# ProDoc___2025-09-02.net
KiCad netlist of a schematic drawn in EasyEDA Pro
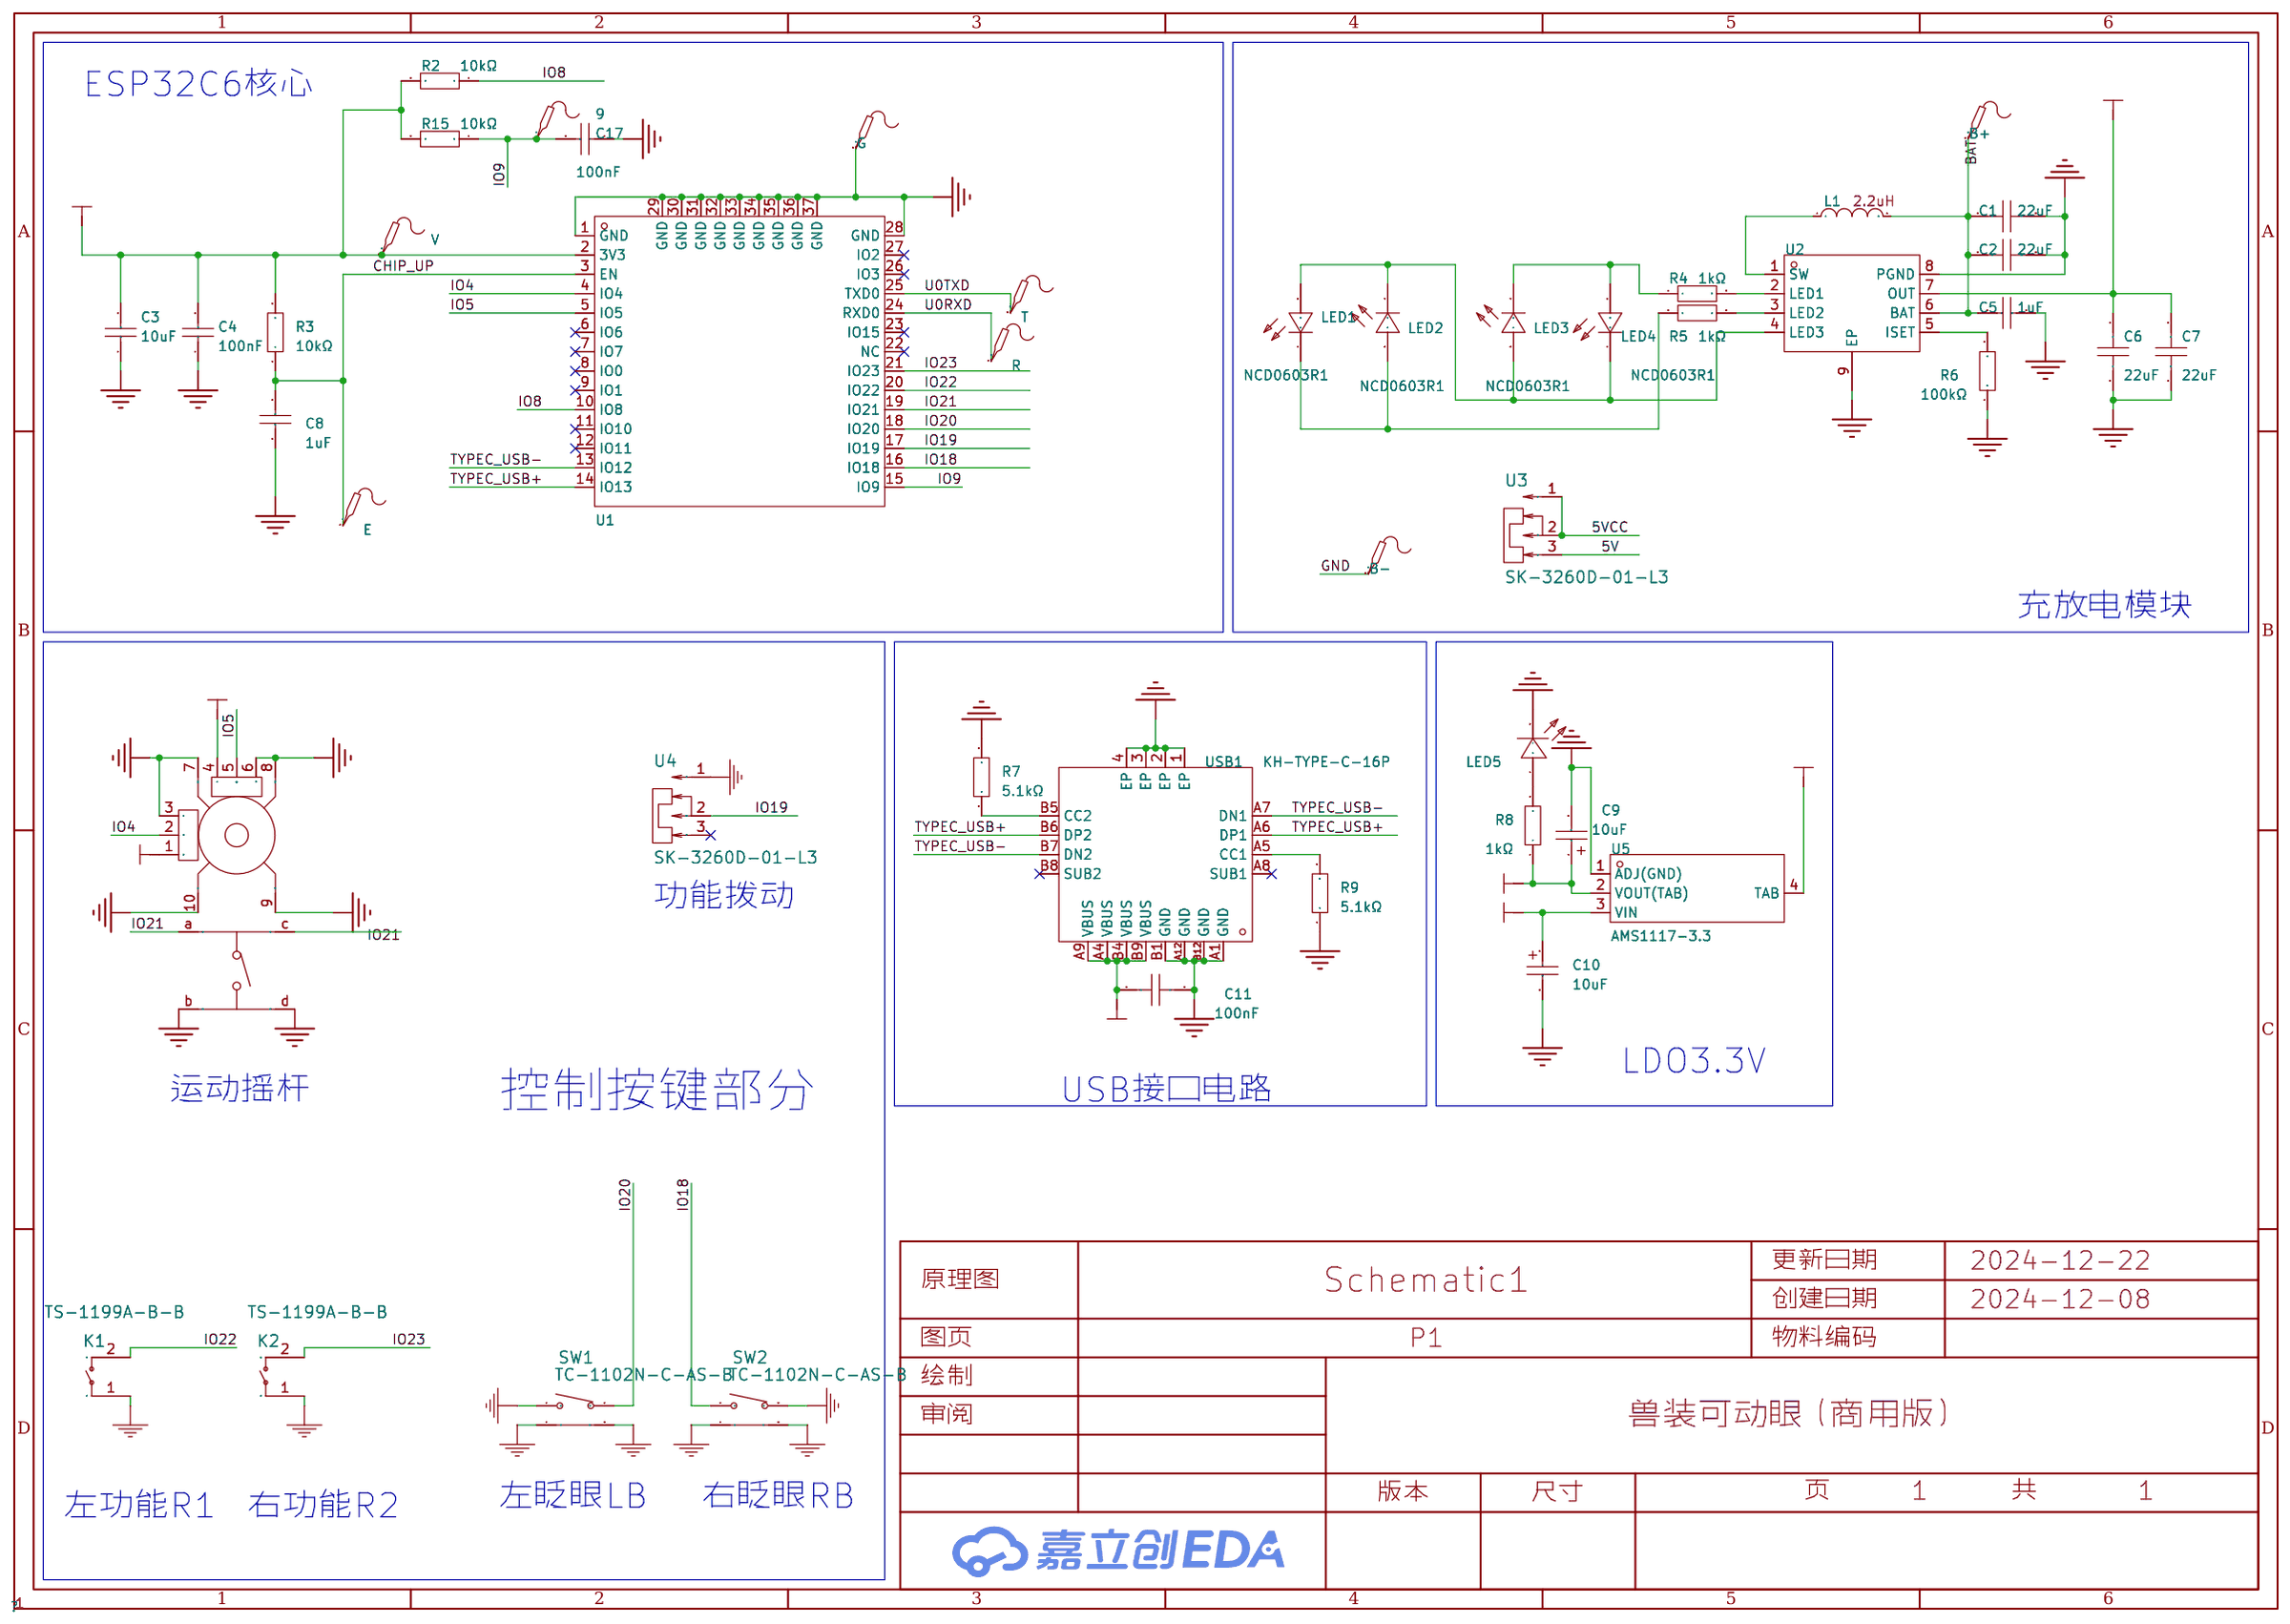
[diagram p0: schematic sheet]

(export (version "E")
  (design (tool "Eeschema 10.0.6"))
  (components
    (comp (ref "9")
      (value "~")
      (footprint "easyedapro:Test-Point-0.5mm")
      (description "Test Point 测试点")
      (libsource (lib "easyedapro") (part "Test-Point"))
    )
    (comp (ref "B+")
      (value "~")
      (footprint "easyedapro:Test-Point-0.5mm")
      (description "Test Point 测试点")
      (libsource (lib "easyedapro") (part "Test-Point"))
    )
    (comp (ref "B-")
      (value "~")
      (footprint "easyedapro:Test-Point-0.5mm")
      (description "Test Point 测试点")
      (libsource (lib "easyedapro") (part "Test-Point"))
    )
    (comp (ref "C1")
      (value "22uF")
      (footprint "easyedapro:C0805")
      (description "容值:22uF;精度:±20%;额定电压:25V;材质(温度系数):X5R;")
      (fields
        (field (name "Manufacturer Part") "CL21A226MAQNNNE")
        (field (name "Manufacturer") "SAMSUNG(三星)")
      )
      (libsource (lib "easyedapro") (part "CL21A226MAQNNNE"))
    )
    (comp (ref "C2")
      (value "22uF")
      (footprint "easyedapro:C0805")
      (description "容值:22uF;精度:±20%;额定电压:25V;材质(温度系数):X5R;")
      (fields
        (field (name "Manufacturer Part") "CL21A226MAQNNNE")
        (field (name "Manufacturer") "SAMSUNG(三星)")
      )
      (libsource (lib "easyedapro") (part "CL21A226MAQNNNE"))
    )
    (comp (ref "C3")
      (value "10uF")
      (footprint "easyedapro:C0805")
      (description "容值:10uF;精度:±10%;额定电压:16V;材质(温度系数):X5R;")
      (fields
        (field (name "Manufacturer Part") "CL21A106KOQNNNE")
        (field (name "Manufacturer") "SAMSUNG(三星)")
      )
      (libsource (lib "easyedapro") (part "CL21A106KOQNNNE"))
    )
    (comp (ref "C4")
      (value "100nF")
      (footprint "easyedapro:C0805")
      (description "容值:100nF;精度:±10%;额定电压:50V;材质(温度系数):X7R;")
      (fields (field (name "Manufacturer Part") "0805B104K500NT") (field (name "Manufacturer") "FH(风华)"))
      (libsource (lib "easyedapro") (part "0805B104K500NT"))
    )
    (comp (ref "C5")
      (value "1uF")
      (footprint "easyedapro:C0603")
      (description "容值:1uF;精度:±10%;额定电压:50V;材质(温度系数):X5R;")
      (fields
        (field (name "Manufacturer Part") "CL10A105KB8NNNC")
        (field (name "Manufacturer") "SAMSUNG(三星)")
      )
      (libsource (lib "easyedapro") (part "CL10A105KB8NNNC"))
    )
    (comp (ref "C6")
      (value "22uF")
      (footprint "easyedapro:C0805")
      (description "容值:22uF;精度:±20%;额定电压:25V;材质(温度系数):X5R;")
      (fields
        (field (name "Manufacturer Part") "CL21A226MAQNNNE")
        (field (name "Manufacturer") "SAMSUNG(三星)")
      )
      (libsource (lib "easyedapro") (part "CL21A226MAQNNNE"))
    )
    (comp (ref "C7")
      (value "22uF")
      (footprint "easyedapro:C0805")
      (description "容值:22uF;精度:±20%;额定电压:25V;材质(温度系数):X5R;")
      (fields
        (field (name "Manufacturer Part") "CL21A226MAQNNNE")
        (field (name "Manufacturer") "SAMSUNG(三星)")
      )
      (libsource (lib "easyedapro") (part "CL21A226MAQNNNE"))
    )
    (comp (ref "C8")
      (value "1uF")
      (footprint "easyedapro:C0805")
      (description "容值:1uF;精度:±10%;额定电压:50V;材质(温度系数):X7R;")
      (fields
        (field (name "Manufacturer Part") "CL21B105KBFNNNE")
        (field (name "Manufacturer") "SAMSUNG(三星)")
      )
      (libsource (lib "easyedapro") (part "CL21B105KBFNNNE"))
    )
    (comp (ref "C9")
      (value "10uF")
      (footprint "easyedapro:CAP-SMD_L3.2-W1.6-RD-C7171")
      (description "容值:10uF;精度:±10%;额定电压:16V;等效串联电阻:3Ω@100kHz;")
      (fields (field (name "Manufacturer Part") "TAJA106K016RNJ") (field (name "Manufacturer") "Kyocera AVX"))
      (libsource (lib "easyedapro") (part "TAJA106K016RNJ"))
    )
    (comp (ref "C10")
      (value "10uF")
      (footprint "easyedapro:CAP-SMD_L3.2-W1.6-RD-C7171")
      (description "容值:10uF;精度:±10%;额定电压:16V;等效串联电阻:3Ω@100kHz;")
      (fields (field (name "Manufacturer Part") "TAJA106K016RNJ") (field (name "Manufacturer") "Kyocera AVX"))
      (libsource (lib "easyedapro") (part "TAJA106K016RNJ"))
    )
    (comp (ref "C11")
      (value "100nF")
      (footprint "easyedapro:C0603")
      (description "容值:100nF;精度:±10%;额定电压:50V;材质(温度系数):X7R;")
      (fields
        (field (name "Manufacturer Part") "CC0603KRX7R9BB104")
        (field (name "Manufacturer") "YAGEO(国巨)")
      )
      (libsource (lib "easyedapro") (part "CC0603KRX7R9BB104"))
    )
    (comp (ref "C17")
      (value "100nF")
      (footprint "easyedapro:C0805")
      (description "容值:100nF;精度:±10%;额定电压:50V;材质(温度系数):X7R;")
      (fields (field (name "Manufacturer Part") "0805B104K500NT") (field (name "Manufacturer") "FH(风华)"))
      (libsource (lib "easyedapro") (part "0805B104K500NT"))
    )
    (comp (ref "E")
      (value "~")
      (footprint "easyedapro:Test-Point-0.5mm")
      (description "Test Point 测试点")
      (libsource (lib "easyedapro") (part "Test-Point"))
    )
    (comp (ref "G")
      (value "~")
      (footprint "easyedapro:Test-Point-0.5mm")
      (description "Test Point 测试点")
      (libsource (lib "easyedapro") (part "Test-Point"))
    )
    (comp (ref "JOY1")
      (value "RKJXV1224005")
      (fields (field (name "Manufacturer") "ALPSALPINE(阿尔卑斯阿尔派)"))
      (libsource (lib "easyedapro") (part "RKJXV1224005"))
    )
    (comp (ref "K1")
      (value "TS-1199A-B-B")
      (footprint "easyedapro:SW-SMD_L6.0-W6.0-P6.00-LS6.6")
      (fields (field (name "Manufacturer") "XKB Connectivity(中国星坤)"))
      (libsource (lib "easyedapro") (part "TS-1199A-B-B"))
    )
    (comp (ref "K2")
      (value "TS-1199A-B-B")
      (footprint "easyedapro:SW-SMD_L6.0-W6.0-P6.00-LS6.6")
      (fields (field (name "Manufacturer") "XKB Connectivity(中国星坤)"))
      (libsource (lib "easyedapro") (part "TS-1199A-B-B"))
    )
    (comp (ref "L1")
      (value "2.2uH")
      (footprint "easyedapro:IND-SMD_L5.2-W5.2_MS0530-3R3M")
      (description "电感值:2.2uH;精度:±20%;额定电流:6.5A;饱和电流(Isat):6.5A;直流电阻(DCR):21.6mΩ;")
      (fields
        (field (name "Manufacturer Part") "MDA5030-2R2M")
        (field (name "Manufacturer") "KOHERelec(科或)")
        (field (name "Capacitance") "2.2uH")
      )
      (libsource (lib "easyedapro") (part "MDA5030-2R2M"))
    )
    (comp (ref "LED1")
      (value "NCD0603R1")
      (footprint "easyedapro:LED0603-RD_RED")
      (fields (field (name "Manufacturer") "国星光电"))
      (libsource (lib "easyedapro") (part "FC-DA1608HRK-620D"))
    )
    (comp (ref "LED2")
      (value "NCD0603R1")
      (footprint "easyedapro:LED0603-RD_RED")
      (fields (field (name "Manufacturer") "国星光电"))
      (libsource (lib "easyedapro") (part "FC-DA1608HRK-620D"))
    )
    (comp (ref "LED3")
      (value "NCD0603R1")
      (footprint "easyedapro:LED0603-RD_RED")
      (fields (field (name "Manufacturer") "国星光电"))
      (libsource (lib "easyedapro") (part "FC-DA1608HRK-620D"))
    )
    (comp (ref "LED4")
      (value "NCD0603R1")
      (footprint "easyedapro:LED0603-RD_RED")
      (fields (field (name "Manufacturer") "国星光电"))
      (libsource (lib "easyedapro") (part "FC-DA1608HRK-620D"))
    )
    (comp (ref "LED5")
      (value "NCD0805R1")
      (footprint "easyedapro:LED0805-R-RD")
      (fields (field (name "Manufacturer") "国星光电"))
      (libsource (lib "easyedapro") (part "FC-2012HRK-620D"))
    )
    (comp (ref "R")
      (value "~")
      (footprint "easyedapro:Test-Point-0.5mm")
      (description "Test Point 测试点")
      (libsource (lib "easyedapro") (part "Test-Point"))
    )
    (comp (ref "R2")
      (value "10kΩ")
      (footprint "easyedapro:R0805")
      (description "电阻类型:厚膜电阻;阻值:10kΩ;精度:±1%;功率:125mW;")
      (fields
        (field (name "Manufacturer Part") "0805W8F1002T5E")
        (field (name "Manufacturer") "UNI-ROYAL(厚声)")
      )
      (libsource (lib "easyedapro") (part "0805W8F1002T5E"))
    )
    (comp (ref "R3")
      (value "10kΩ")
      (footprint "easyedapro:R0805")
      (description "电阻类型:厚膜电阻;阻值:10kΩ;精度:±1%;功率:125mW;")
      (fields
        (field (name "Manufacturer Part") "0805W8F1002T5E")
        (field (name "Manufacturer") "UNI-ROYAL(厚声)")
      )
      (libsource (lib "easyedapro") (part "0805W8F1002T5E"))
    )
    (comp (ref "R4")
      (value "1kΩ")
      (footprint "easyedapro:R0603")
      (description "电阻类型:厚膜电阻;阻值:1kΩ;精度:±1%;功率:100mW;")
      (fields
        (field (name "Manufacturer Part") "0603WAF1001T5E")
        (field (name "Manufacturer") "UNI-ROYAL(厚声)")
      )
      (libsource (lib "easyedapro") (part "0603WAF1001T5E"))
    )
    (comp (ref "R5")
      (value "1kΩ")
      (footprint "easyedapro:R0603")
      (description "电阻类型:厚膜电阻;阻值:1kΩ;精度:±1%;功率:100mW;")
      (fields
        (field (name "Manufacturer Part") "0603WAF1001T5E")
        (field (name "Manufacturer") "UNI-ROYAL(厚声)")
      )
      (libsource (lib "easyedapro") (part "0603WAF1001T5E"))
    )
    (comp (ref "R6")
      (value "100kΩ")
      (footprint "easyedapro:R0603")
      (description "电阻类型:厚膜电阻;阻值:100kΩ;精度:±1%;功率:100mW;")
      (fields
        (field (name "Manufacturer Part") "0603WAF1003T5E")
        (field (name "Manufacturer") "UNI-ROYAL(厚声)")
      )
      (libsource (lib "easyedapro") (part "0603WAF1003T5E"))
    )
    (comp (ref "R7")
      (value "5.1kΩ")
      (footprint "easyedapro:R0603")
      (description "电阻类型:厚膜电阻;阻值:5.1kΩ;精度:±1%;功率:100mW;最大工作电压:75V;温度系数:±100ppm/°C;")
      (fields
        (field (name "Manufacturer Part") "0603WAF5101T5E")
        (field (name "Manufacturer") "UNI-ROYAL(厚声)")
      )
      (libsource (lib "easyedapro") (part "0603WAF5101T5E"))
    )
    (comp (ref "R8")
      (value "1kΩ")
      (footprint "easyedapro:R0805")
      (description "电阻类型:厚膜电阻;阻值:1kΩ;精度:±1%;功率:125mW;")
      (fields (field (name "Manufacturer Part") "RC0805FR-071KL") (field (name "Manufacturer") "YAGEO(国巨)"))
      (libsource (lib "easyedapro") (part "RC0805FR-071KL"))
    )
    (comp (ref "R9")
      (value "5.1kΩ")
      (footprint "easyedapro:R0603")
      (description "电阻类型:厚膜电阻;阻值:5.1kΩ;精度:±1%;功率:100mW;最大工作电压:75V;温度系数:±100ppm/°C;")
      (fields
        (field (name "Manufacturer Part") "0603WAF5101T5E")
        (field (name "Manufacturer") "UNI-ROYAL(厚声)")
      )
      (libsource (lib "easyedapro") (part "0603WAF5101T5E"))
    )
    (comp (ref "R15")
      (value "10kΩ")
      (footprint "easyedapro:R0805")
      (description "电阻类型:厚膜电阻;阻值:10kΩ;精度:±1%;功率:125mW;")
      (fields
        (field (name "Manufacturer Part") "0805W8F1002T5E")
        (field (name "Manufacturer") "UNI-ROYAL(厚声)")
      )
      (libsource (lib "easyedapro") (part "0805W8F1002T5E"))
    )
    (comp (ref "SW1")
      (value "TC-1102N-C-AS-B")
      (footprint "easyedapro:SW-TH_TC-1102N-C-AS-B")
      (fields (field (name "Manufacturer") "XKB Connectivity(中国星坤)"))
      (libsource (lib "easyedapro") (part "TC-1102N-C-AS-B"))
    )
    (comp (ref "SW2")
      (value "TC-1102N-C-AS-B")
      (footprint "easyedapro:SW-TH_TC-1102N-C-AS-B")
      (fields (field (name "Manufacturer") "XKB Connectivity(中国星坤)"))
      (libsource (lib "easyedapro") (part "TC-1102N-C-AS-B"))
    )
    (comp (ref "T")
      (value "~")
      (footprint "easyedapro:Test-Point-0.5mm")
      (description "Test Point 测试点")
      (libsource (lib "easyedapro") (part "Test-Point"))
    )
    (comp (ref "U1")
      (value "ESP32-C6-WROOM-1-N8")
      (footprint "easyedapro:WIRELM-SMD_ESP32-C6-WROOM-1")
      (fields (field (name "Manufacturer") "ESPRESSIF(乐鑫)"))
      (libsource (lib "easyedapro") (part "ESP32-C6-WROOM-1-N8"))
    )
    (comp (ref "U2")
      (value "ETA9740")
      (footprint "easyedapro:ESOP-8_L4.9-W3.9-P1.27-LS6.0-BL-EP")
      (libsource (lib "easyedapro") (part "ETA9740"))
    )
    (comp (ref "U3")
      (value "SK-3260D-01-L3")
      (footprint "easyedapro:SW-TH_SK-3260D-01-LX")
      (description "电路结构:单刀双掷;安装方式:侧插;开关颜色:黑色;额定电流(DC):50mA;额定电压(DC):12V;额定电流(AC):50mA;额定电压(AC):12V;机械寿命:1万次;")
      (fields (field (name "Manufacturer") "XKB Connectivity(中国星坤)"))
      (libsource (lib "easyedapro") (part "SK-3260D-01-L3"))
    )
    (comp (ref "U4")
      (value "SK-3260D-01-L3")
      (footprint "easyedapro:SW-TH_SK-3260D-01-LX")
      (description "电路结构:单刀双掷;安装方式:侧插;开关颜色:黑色;额定电流(DC):50mA;额定电压(DC):12V;额定电流(AC):50mA;额定电压(AC):12V;机械寿命:1万次;")
      (fields (field (name "Manufacturer") "XKB Connectivity(中国星坤)"))
      (libsource (lib "easyedapro") (part "SK-3260D-01-L3"))
    )
    (comp (ref "U5")
      (value "AMS1117-3.3")
      (footprint "easyedapro:SOT-223-4_L6.5-W3.5-P2.30-LS7.0-BR")
      (description "输出类型:固定;最大输入电压:18V;输出电压:3.3V;输出电流:1A;电源纹波抑制比(PSRR):60dB@(120Hz);输出极性:正极;")
      (fields (field (name "Manufacturer") "UMW(友台半导体)"))
      (libsource (lib "easyedapro") (part "AMS1117-3.3_C347222"))
    )
    (comp (ref "USB1")
      (value "KH-TYPE-C-16P")
      (footprint "easyedapro:USB-C-SMD_KH-TYPE-C-16P")
      (description "连接器类型:Type-C;标准:-;公母:母座;触点数量:16;端口数量:1;安装方式:卧贴;额定电流 - 电源:3A;工作温度范围:-40°C~+85°C;")
      (fields (field (name "Manufacturer") "kinghelm(金航标)"))
      (libsource (lib "easyedapro") (part "KH-TYPE-C-16P"))
    )
    (comp (ref "V")
      (value "~")
      (footprint "easyedapro:Test-Point-0.5mm")
      (description "Test Point 测试点")
      (libsource (lib "easyedapro") (part "Test-Point"))
    )
  )
  (nets
    (net (code "1") (name "/BAT") (class "Default")
      (node (ref "B+") (pin "1") (pinfunction "1_1") (pintype "input"))
      (node (ref "C1") (pin "1") (pinfunction "1_1") (pintype "input"))
      (node (ref "C2") (pin "1") (pinfunction "1_1") (pintype "input"))
      (node (ref "C5") (pin "1") (pinfunction "1_1") (pintype "input"))
      (node (ref "L1") (pin "2") (pinfunction "2_2") (pintype "unspecified"))
      (node (ref "U2") (pin "6") (pinfunction "BAT_6") (pintype "input"))
    )
    (net (code "2") (name "/CHIP_UP") (class "Default")
      (node (ref "C8") (pin "2") (pinfunction "2_2") (pintype "input"))
      (node (ref "E") (pin "1") (pinfunction "1_1") (pintype "input"))
      (node (ref "R3") (pin "1") (pinfunction "1_1") (pintype "input"))
      (node (ref "U1") (pin "3") (pinfunction "EN_3") (pintype "unspecified"))
    )
    (net (code "3") (name "/IO4") (class "Default")
      (node (ref "JOY1") (pin "2") (pinfunction "DTA_2") (pintype "input"))
      (node (ref "U1") (pin "4") (pinfunction "IO4_4") (pintype "unspecified"))
    )
    (net (code "4") (name "/IO5") (class "Default")
      (node (ref "JOY1") (pin "5") (pinfunction "DTA_5") (pintype "input"))
      (node (ref "U1") (pin "5") (pinfunction "IO5_5") (pintype "unspecified"))
    )
    (net (code "5") (name "/IO8") (class "Default")
      (node (ref "R2") (pin "1") (pinfunction "1_1") (pintype "input"))
      (node (ref "U1") (pin "10") (pinfunction "IO8_10") (pintype "unspecified"))
    )
    (net (code "6") (name "/IO9") (class "Default")
      (node (ref "9") (pin "1") (pinfunction "1_1") (pintype "input"))
      (node (ref "C17") (pin "2") (pinfunction "2_2") (pintype "input"))
      (node (ref "R15") (pin "1") (pinfunction "1_1") (pintype "input"))
      (node (ref "U1") (pin "15") (pinfunction "IO9_15") (pintype "unspecified"))
    )
    (net (code "7") (name "/IO18") (class "Default")
      (node (ref "SW2") (pin "1") (pinfunction "1_1") (pintype "input"))
      (node (ref "U1") (pin "16") (pinfunction "IO18_16") (pintype "unspecified"))
    )
    (net (code "8") (name "/IO19") (class "Default")
      (node (ref "U1") (pin "17") (pinfunction "IO19_17") (pintype "unspecified"))
      (node (ref "U4") (pin "2") (pinfunction "2_2") (pintype "unspecified"))
    )
    (net (code "9") (name "/IO20") (class "Default")
      (node (ref "SW1") (pin "2") (pinfunction "2_2") (pintype "input"))
      (node (ref "U1") (pin "18") (pinfunction "IO20_18") (pintype "unspecified"))
    )
    (net (code "10") (name "/IO21") (class "Default")
      (node (ref "JOY1") (pin "a") (pinfunction "a_a") (pintype "input"))
      (node (ref "JOY1") (pin "c") (pinfunction "c_c") (pintype "input"))
      (node (ref "U1") (pin "19") (pinfunction "IO21_19") (pintype "unspecified"))
    )
    (net (code "11") (name "/IO22") (class "Default")
      (node (ref "K1") (pin "2") (pinfunction "2_2") (pintype "unspecified"))
      (node (ref "U1") (pin "20") (pinfunction "IO22_20") (pintype "unspecified"))
    )
    (net (code "12") (name "/IO23") (class "Default")
      (node (ref "K2") (pin "2") (pinfunction "2_2") (pintype "unspecified"))
      (node (ref "U1") (pin "21") (pinfunction "IO23_21") (pintype "unspecified"))
    )
    (net (code "13") (name "/TYPEC_USB+") (class "Default")
      (node (ref "U1") (pin "14") (pinfunction "IO13_14") (pintype "unspecified"))
      (node (ref "USB1") (pin "A6") (pinfunction "DP1_A6") (pintype "input"))
      (node (ref "USB1") (pin "B6") (pinfunction "DP2_B6") (pintype "input"))
    )
    (net (code "14") (name "/TYPEC_USB-") (class "Default")
      (node (ref "U1") (pin "13") (pinfunction "IO12_13") (pintype "unspecified"))
      (node (ref "USB1") (pin "A7") (pinfunction "DN1_A7") (pintype "input"))
      (node (ref "USB1") (pin "B7") (pinfunction "DN2_B7") (pintype "input"))
    )
    (net (code "15") (name "/U0RXD") (class "Default")
      (node (ref "R") (pin "1") (pinfunction "1_1") (pintype "input"))
      (node (ref "U1") (pin "24") (pinfunction "RXD0_24") (pintype "unspecified"))
    )
    (net (code "16") (name "/U0TXD") (class "Default")
      (node (ref "T") (pin "1") (pinfunction "1_1") (pintype "input"))
      (node (ref "U1") (pin "25") (pinfunction "TXD0_25") (pintype "unspecified"))
    )
    (net (code "17") (name "3V3") (class "Default")
      (node (ref "C3") (pin "2") (pinfunction "2_2") (pintype "input"))
      (node (ref "C4") (pin "2") (pinfunction "2_2") (pintype "input"))
      (node (ref "C9") (pin "1") (pinfunction "1_1") (pintype "input"))
      (node (ref "JOY1") (pin "1") (pinfunction "B_1") (pintype "input"))
      (node (ref "JOY1") (pin "4") (pinfunction "A_4") (pintype "input"))
      (node (ref "R15") (pin "2") (pinfunction "2_2") (pintype "input"))
      (node (ref "R2") (pin "2") (pinfunction "2_2") (pintype "input"))
      (node (ref "R3") (pin "2") (pinfunction "2_2") (pintype "input"))
      (node (ref "R8") (pin "1") (pinfunction "1_1") (pintype "input"))
      (node (ref "U1") (pin "2") (pinfunction "3V3_2") (pintype "unspecified"))
      (node (ref "U5") (pin "2") (pinfunction "VOUT(TAB)_2") (pintype "input"))
      (node (ref "U5") (pin "4") (pinfunction "TAB_4") (pintype "input"))
      (node (ref "V") (pin "1") (pinfunction "1_1") (pintype "input"))
    )
    (net (code "18") (name "5V") (class "Default")
      (node (ref "C11") (pin "2") (pinfunction "2_2") (pintype "unspecified"))
      (node (ref "C6") (pin "1") (pinfunction "1_1") (pintype "input"))
      (node (ref "C7") (pin "2") (pinfunction "2_2") (pintype "input"))
      (node (ref "U2") (pin "7") (pinfunction "OUT_7") (pintype "input"))
      (node (ref "U3") (pin "3") (pinfunction "3_3") (pintype "unspecified"))
      (node (ref "USB1") (pin "A4") (pinfunction "VBUS_A4") (pintype "input"))
      (node (ref "USB1") (pin "A9") (pinfunction "VBUS_A9") (pintype "input"))
      (node (ref "USB1") (pin "B4") (pinfunction "VBUS_B4") (pintype "input"))
      (node (ref "USB1") (pin "B9") (pinfunction "VBUS_B9") (pintype "input"))
    )
    (net (code "19") (name "5VCC") (class "Default")
      (node (ref "C10") (pin "1") (pinfunction "1_1") (pintype "input"))
      (node (ref "U3") (pin "1") (pinfunction "1_1") (pintype "unspecified"))
      (node (ref "U3") (pin "2") (pinfunction "2_2") (pintype "unspecified"))
      (node (ref "U5") (pin "3") (pinfunction "VIN_3") (pintype "input"))
    )
    (net (code "20") (name "GND") (class "Default")
      (node (ref "B-") (pin "1") (pinfunction "1_1") (pintype "input"))
      (node (ref "C1") (pin "2") (pinfunction "2_2") (pintype "input"))
      (node (ref "C10") (pin "2") (pinfunction "2_2") (pintype "input"))
      (node (ref "C11") (pin "1") (pinfunction "1_1") (pintype "unspecified"))
      (node (ref "C17") (pin "1") (pinfunction "1_1") (pintype "input"))
      (node (ref "C2") (pin "2") (pinfunction "2_2") (pintype "input"))
      (node (ref "C3") (pin "1") (pinfunction "1_1") (pintype "input"))
      (node (ref "C4") (pin "1") (pinfunction "1_1") (pintype "input"))
      (node (ref "C5") (pin "2") (pinfunction "2_2") (pintype "input"))
      (node (ref "C6") (pin "2") (pinfunction "2_2") (pintype "input"))
      (node (ref "C7") (pin "1") (pinfunction "1_1") (pintype "input"))
      (node (ref "C8") (pin "1") (pinfunction "1_1") (pintype "input"))
      (node (ref "C9") (pin "2") (pinfunction "2_2") (pintype "input"))
      (node (ref "G") (pin "1") (pinfunction "1_1") (pintype "input"))
      (node (ref "JOY1") (pin "10") (pinfunction "GND_10") (pintype "input"))
      (node (ref "JOY1") (pin "3") (pinfunction "A_3") (pintype "input"))
      (node (ref "JOY1") (pin "6") (pinfunction "B_6") (pintype "input"))
      (node (ref "JOY1") (pin "7") (pinfunction "GND_7") (pintype "input"))
      (node (ref "JOY1") (pin "8") (pinfunction "GND_8") (pintype "input"))
      (node (ref "JOY1") (pin "9") (pinfunction "GND_9") (pintype "input"))
      (node (ref "JOY1") (pin "b") (pinfunction "b_b") (pintype "input"))
      (node (ref "JOY1") (pin "d") (pinfunction "d_d") (pintype "input"))
      (node (ref "K1") (pin "1") (pinfunction "1_1") (pintype "unspecified"))
      (node (ref "K2") (pin "1") (pinfunction "1_1") (pintype "unspecified"))
      (node (ref "LED5") (pin "2") (pinfunction "-_2") (pintype "unspecified"))
      (node (ref "R6") (pin "1") (pinfunction "1_1") (pintype "input"))
      (node (ref "R7") (pin "2") (pinfunction "2_2") (pintype "input"))
      (node (ref "R9") (pin "1") (pinfunction "1_1") (pintype "input"))
      (node (ref "SW1") (pin "1") (pinfunction "1_1") (pintype "input"))
      (node (ref "SW1") (pin "3") (pinfunction "3_3") (pintype "input"))
      (node (ref "SW1") (pin "4") (pinfunction "4_4") (pintype "input"))
      (node (ref "SW2") (pin "2") (pinfunction "2_2") (pintype "input"))
      (node (ref "SW2") (pin "3") (pinfunction "3_3") (pintype "input"))
      (node (ref "SW2") (pin "4") (pinfunction "4_4") (pintype "input"))
      (node (ref "U1") (pin "1") (pinfunction "GND_1") (pintype "unspecified"))
      (node (ref "U1") (pin "28") (pinfunction "GND_28") (pintype "unspecified"))
      (node (ref "U1") (pin "29") (pinfunction "GND_29") (pintype "unspecified"))
      (node (ref "U1") (pin "30") (pinfunction "GND_30") (pintype "unspecified"))
      (node (ref "U1") (pin "31") (pinfunction "GND_31") (pintype "unspecified"))
      (node (ref "U1") (pin "32") (pinfunction "GND_32") (pintype "unspecified"))
      (node (ref "U1") (pin "33") (pinfunction "GND_33") (pintype "unspecified"))
      (node (ref "U1") (pin "34") (pinfunction "GND_34") (pintype "unspecified"))
      (node (ref "U1") (pin "35") (pinfunction "GND_35") (pintype "unspecified"))
      (node (ref "U1") (pin "36") (pinfunction "GND_36") (pintype "unspecified"))
      (node (ref "U1") (pin "37") (pinfunction "GND_37") (pintype "unspecified"))
      (node (ref "U2") (pin "8") (pinfunction "PGND_8") (pintype "input"))
      (node (ref "U2") (pin "9") (pinfunction "EP_9") (pintype "input"))
      (node (ref "U4") (pin "1") (pinfunction "1_1") (pintype "unspecified"))
      (node (ref "U5") (pin "1") (pinfunction "ADJ(GND)_1") (pintype "input"))
      (node (ref "USB1") (pin "1") (pinfunction "EP_1") (pintype "input"))
      (node (ref "USB1") (pin "2") (pinfunction "EP_2") (pintype "input"))
      (node (ref "USB1") (pin "3") (pinfunction "EP_3") (pintype "input"))
      (node (ref "USB1") (pin "4") (pinfunction "EP_4") (pintype "input"))
      (node (ref "USB1") (pin "A1") (pinfunction "GND_A1") (pintype "input"))
      (node (ref "USB1") (pin "A12") (pinfunction "GND_A12") (pintype "input"))
      (node (ref "USB1") (pin "B1") (pinfunction "GND_B1") (pintype "input"))
      (node (ref "USB1") (pin "B12") (pinfunction "GND_B12") (pintype "input"))
    )
    (net (code "21") (name "Net-(LED1-A)") (class "Default")
      (node (ref "LED1") (pin "2") (pinfunction "A_2") (pintype "input"))
      (node (ref "LED2") (pin "1") (pinfunction "K_1") (pintype "input"))
      (node (ref "LED3") (pin "2") (pinfunction "A_2") (pintype "input"))
      (node (ref "LED4") (pin "1") (pinfunction "K_1") (pintype "input"))
      (node (ref "U2") (pin "4") (pinfunction "LED3_4") (pintype "input"))
    )
    (net (code "22") (name "Net-(LED1-K)") (class "Default")
      (node (ref "LED1") (pin "1") (pinfunction "K_1") (pintype "input"))
      (node (ref "LED2") (pin "2") (pinfunction "A_2") (pintype "input"))
      (node (ref "R5") (pin "1") (pinfunction "1_1") (pintype "input"))
    )
    (net (code "23") (name "Net-(LED3-K)") (class "Default")
      (node (ref "LED3") (pin "1") (pinfunction "K_1") (pintype "input"))
      (node (ref "LED4") (pin "2") (pinfunction "A_2") (pintype "input"))
      (node (ref "R4") (pin "1") (pinfunction "1_1") (pintype "input"))
    )
    (net (code "24") (name "Net-(LED5-+)") (class "Default")
      (node (ref "LED5") (pin "1") (pinfunction "+_1") (pintype "unspecified"))
      (node (ref "R8") (pin "2") (pinfunction "2_2") (pintype "input"))
    )
    (net (code "25") (name "Net-(U2-ISET)") (class "Default")
      (node (ref "R6") (pin "2") (pinfunction "2_2") (pintype "input"))
      (node (ref "U2") (pin "5") (pinfunction "ISET_5") (pintype "input"))
    )
    (net (code "26") (name "Net-(U2-LED1)") (class "Default")
      (node (ref "R4") (pin "2") (pinfunction "2_2") (pintype "input"))
      (node (ref "U2") (pin "2") (pinfunction "LED1_2") (pintype "input"))
    )
    (net (code "27") (name "Net-(U2-LED2)") (class "Default")
      (node (ref "R5") (pin "2") (pinfunction "2_2") (pintype "input"))
      (node (ref "U2") (pin "3") (pinfunction "LED2_3") (pintype "input"))
    )
    (net (code "28") (name "Net-(U2-SW)") (class "Default")
      (node (ref "L1") (pin "1") (pinfunction "1_1") (pintype "unspecified"))
      (node (ref "U2") (pin "1") (pinfunction "SW_1") (pintype "input"))
    )
    (net (code "29") (name "Net-(USB1-CC1)") (class "Default")
      (node (ref "R9") (pin "2") (pinfunction "2_2") (pintype "input"))
      (node (ref "USB1") (pin "A5") (pinfunction "CC1_A5") (pintype "input"))
    )
    (net (code "30") (name "Net-(USB1-CC2)") (class "Default")
      (node (ref "R7") (pin "1") (pinfunction "1_1") (pintype "input"))
      (node (ref "USB1") (pin "B5") (pinfunction "CC2_B5") (pintype "input"))
    )
    (net (code "31") (name "unconnected-(U1-IO0-Pad8)") (class "Default")
      (node (ref "U1") (pin "8") (pinfunction "IO0_8") (pintype "unspecified+no_connect"))
    )
    (net (code "32") (name "unconnected-(U1-IO1-Pad9)") (class "Default")
      (node (ref "U1") (pin "9") (pinfunction "IO1_9") (pintype "unspecified+no_connect"))
    )
    (net (code "33") (name "unconnected-(U1-IO2-Pad27)") (class "Default")
      (node (ref "U1") (pin "27") (pinfunction "IO2_27") (pintype "unspecified+no_connect"))
    )
    (net (code "34") (name "unconnected-(U1-IO3-Pad26)") (class "Default")
      (node (ref "U1") (pin "26") (pinfunction "IO3_26") (pintype "unspecified+no_connect"))
    )
    (net (code "35") (name "unconnected-(U1-IO6-Pad6)") (class "Default")
      (node (ref "U1") (pin "6") (pinfunction "IO6_6") (pintype "unspecified+no_connect"))
    )
    (net (code "36") (name "unconnected-(U1-IO7-Pad7)") (class "Default")
      (node (ref "U1") (pin "7") (pinfunction "IO7_7") (pintype "unspecified+no_connect"))
    )
    (net (code "37") (name "unconnected-(U1-IO10-Pad11)") (class "Default")
      (node (ref "U1") (pin "11") (pinfunction "IO10_11") (pintype "unspecified+no_connect"))
    )
    (net (code "38") (name "unconnected-(U1-IO11-Pad12)") (class "Default")
      (node (ref "U1") (pin "12") (pinfunction "IO11_12") (pintype "unspecified+no_connect"))
    )
    (net (code "39") (name "unconnected-(U1-IO15-Pad23)") (class "Default")
      (node (ref "U1") (pin "23") (pinfunction "IO15_23") (pintype "unspecified+no_connect"))
    )
    (net (code "40") (name "unconnected-(U1-NC-Pad22)") (class "Default")
      (node (ref "U1") (pin "22") (pinfunction "NC_22") (pintype "unspecified+no_connect"))
    )
    (net (code "41") (name "unconnected-(U4-Pad3)") (class "Default")
      (node (ref "U4") (pin "3") (pinfunction "3_3") (pintype "unspecified+no_connect"))
    )
    (net (code "42") (name "unconnected-(USB1-SUB1-PadA8)") (class "Default")
      (node (ref "USB1") (pin "A8") (pinfunction "SUB1_A8") (pintype "input+no_connect"))
    )
    (net (code "43") (name "unconnected-(USB1-SUB2-PadB8)") (class "Default")
      (node (ref "USB1") (pin "B8") (pinfunction "SUB2_B8") (pintype "input+no_connect"))
    )
  )
)
